# rpi.net
KiCad netlist of a schematic drawn in EAGLE
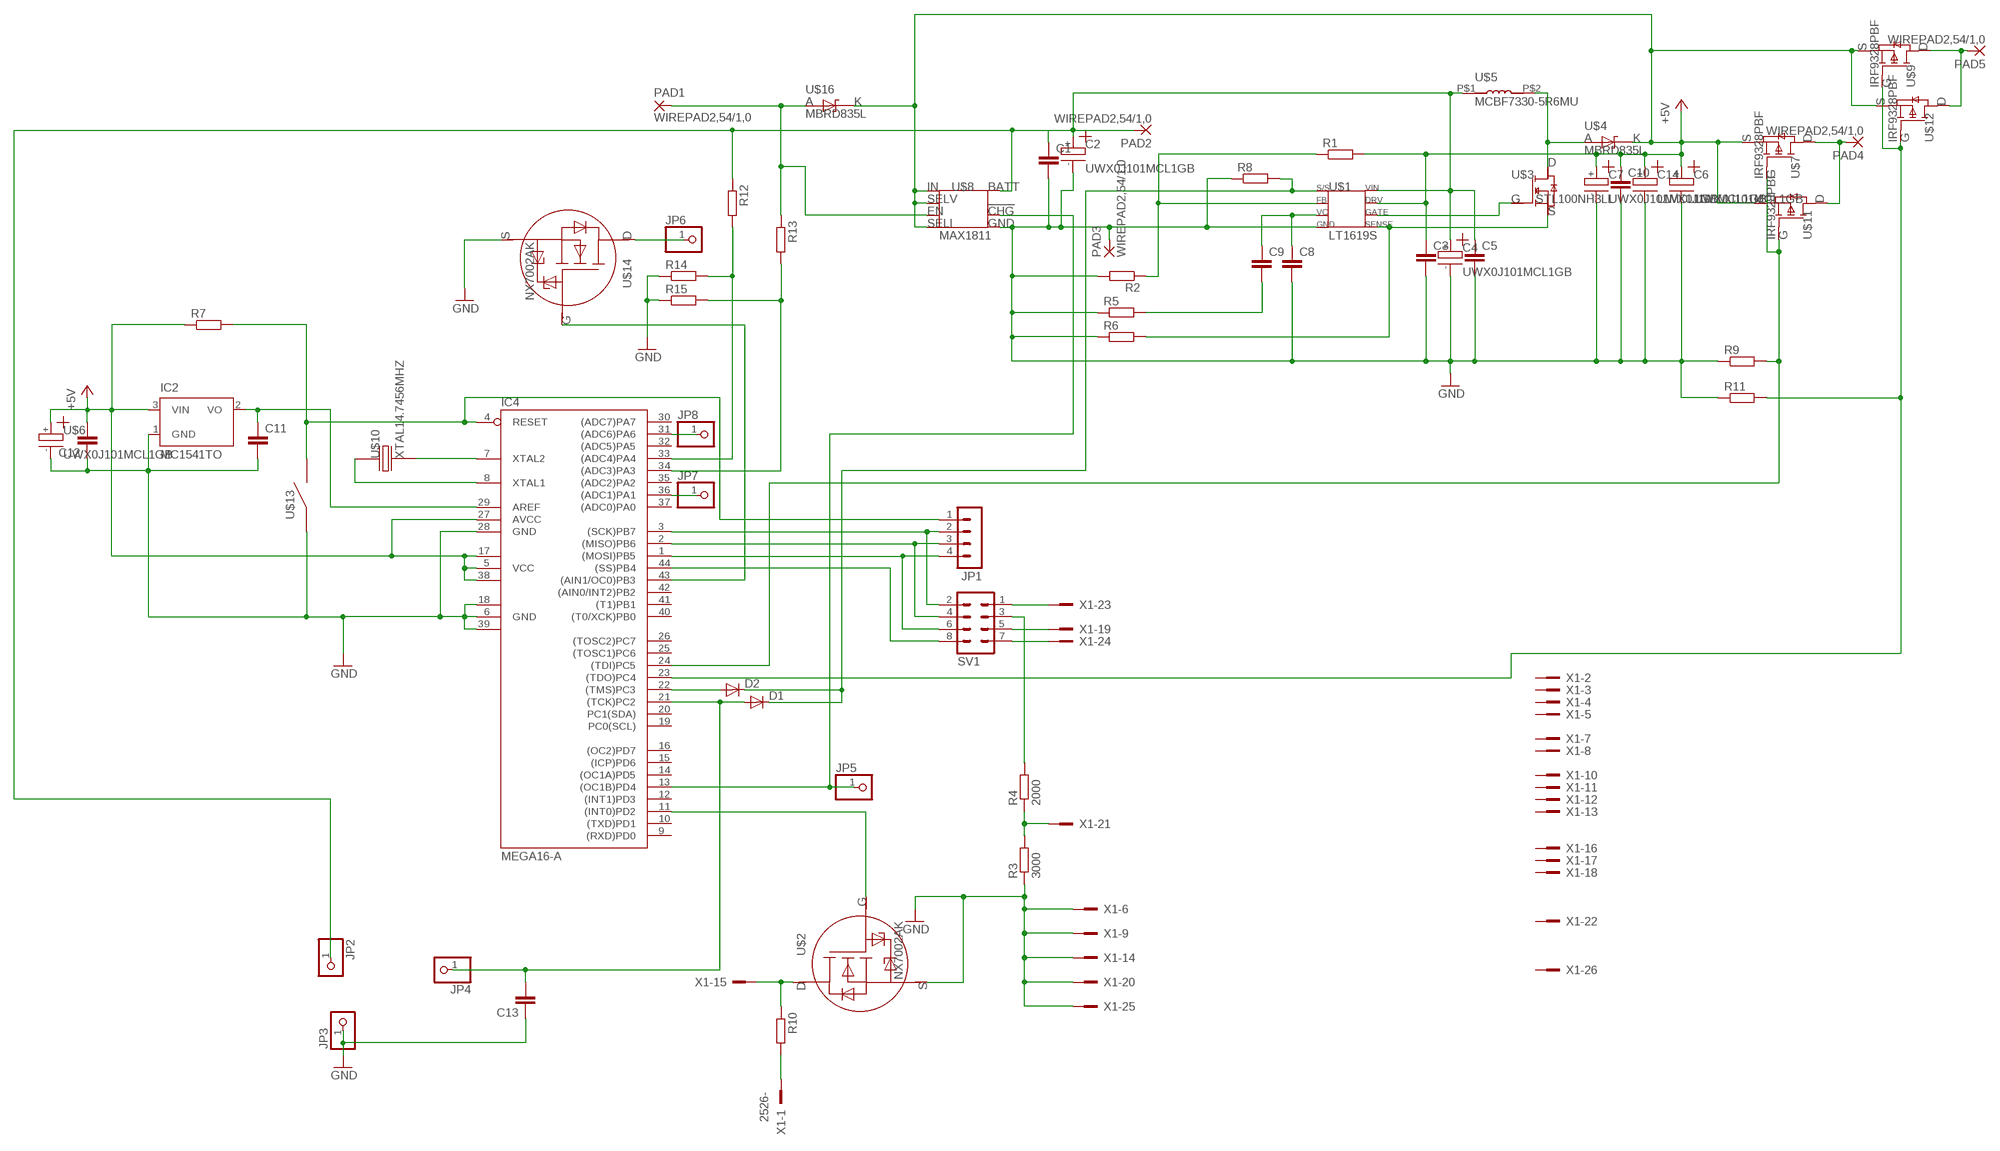
[diagram p0: schematic, sheet 1]

(export (version "E")
  (design (tool "Eeschema 10.0.6"))
  (components
    (comp (ref "C1")
      (value "C-EUC1206")
      (footprint "eagle-import:C1206")
      (libsource (lib "eagle-import") (part "C-EUC1206"))
    )
    (comp (ref "C2")
      (value "UWX0J101MCL1GB")
      (footprint "eagle-import:UWX0J101MCL1GB")
      (libsource (lib "eagle-import") (part "UWX0J101MCL1GB"))
    )
    (comp (ref "C3")
      (value "C-EUC1206")
      (footprint "eagle-import:C1206")
      (libsource (lib "eagle-import") (part "C-EUC1206"))
    )
    (comp (ref "C4")
      (value "UWX0J101MCL1GB")
      (footprint "eagle-import:UWX0J101MCL1GB")
      (libsource (lib "eagle-import") (part "UWX0J101MCL1GB"))
    )
    (comp (ref "C5")
      (value "C-EUC1206")
      (footprint "eagle-import:C1206")
      (libsource (lib "eagle-import") (part "C-EUC1206"))
    )
    (comp (ref "C6")
      (value "UWX0J101MCL1GB")
      (footprint "eagle-import:UWX0J101MCL1GB")
      (libsource (lib "eagle-import") (part "UWX0J101MCL1GB"))
    )
    (comp (ref "C7")
      (value "UWX0J101MCL1GB")
      (footprint "eagle-import:UWX0J101MCL1GB")
      (libsource (lib "eagle-import") (part "UWX0J101MCL1GB"))
    )
    (comp (ref "C8")
      (value "C-EUC1206")
      (footprint "eagle-import:C1206")
      (libsource (lib "eagle-import") (part "C-EUC1206"))
    )
    (comp (ref "C9")
      (value "C-EUC1206")
      (footprint "eagle-import:C1206")
      (libsource (lib "eagle-import") (part "C-EUC1206"))
    )
    (comp (ref "C10")
      (value "C-EUC1206")
      (footprint "eagle-import:C1206")
      (libsource (lib "eagle-import") (part "C-EUC1206"))
    )
    (comp (ref "C11")
      (value "C-EUC1206")
      (footprint "eagle-import:C1206")
      (libsource (lib "eagle-import") (part "C-EUC1206"))
    )
    (comp (ref "C12")
      (value "C-EUC1206")
      (footprint "eagle-import:C1206")
      (libsource (lib "eagle-import") (part "C-EUC1206"))
    )
    (comp (ref "C13")
      (value "C-EUC1206")
      (footprint "eagle-import:C1206")
      (libsource (lib "eagle-import") (part "C-EUC1206"))
    )
    (comp (ref "C14")
      (value "UWX0J101MCL1GB")
      (footprint "eagle-import:UWX0J101MCL1GB")
      (libsource (lib "eagle-import") (part "UWX0J101MCL1GB"))
    )
    (comp (ref "D1")
      (value "DIODE-MINIMELF")
      (footprint "eagle-import:MINIMELF")
      (libsource (lib "eagle-import") (part "DIODE-MINIMELF"))
    )
    (comp (ref "D2")
      (value "DIODE-MINIMELF")
      (footprint "eagle-import:MINIMELF")
      (libsource (lib "eagle-import") (part "DIODE-MINIMELF"))
    )
    (comp (ref "IC2")
      (value "MC1541TO")
      (footprint "eagle-import:TO92")
      (libsource (lib "eagle-import") (part "MC15TO41"))
    )
    (comp (ref "IC4")
      (value "MEGA16-A")
      (footprint "eagle-import:TQFP44")
      (fields (field (name "MPN") "ATMEGA16-16AU"))
      (libsource (lib "eagle-import") (part "MEGA16-A"))
    )
    (comp (ref "JP1")
      (value "MA04-1")
      (footprint "eagle-import:MA04-1")
      (libsource (lib "eagle-import") (part "MA04-1"))
    )
    (comp (ref "JP2")
      (value "PINHD-1X1")
      (footprint "eagle-import:1X01")
      (libsource (lib "eagle-import") (part "PINHD-1X1"))
    )
    (comp (ref "JP3")
      (value "PINHD-1X1")
      (footprint "eagle-import:1X01")
      (libsource (lib "eagle-import") (part "PINHD-1X1"))
    )
    (comp (ref "JP4")
      (value "PINHD-1X1")
      (footprint "eagle-import:1X01")
      (libsource (lib "eagle-import") (part "PINHD-1X1"))
    )
    (comp (ref "JP5")
      (value "PINHD-1X1")
      (footprint "eagle-import:1X01")
      (libsource (lib "eagle-import") (part "PINHD-1X1"))
    )
    (comp (ref "JP6")
      (value "PINHD-1X1")
      (footprint "eagle-import:1X01")
      (libsource (lib "eagle-import") (part "PINHD-1X1"))
    )
    (comp (ref "JP7")
      (value "PINHD-1X1")
      (footprint "eagle-import:1X01")
      (libsource (lib "eagle-import") (part "PINHD-1X1"))
    )
    (comp (ref "JP8")
      (value "PINHD-1X1")
      (footprint "eagle-import:1X01")
      (libsource (lib "eagle-import") (part "PINHD-1X1"))
    )
    (comp (ref "PAD1")
      (value "WIREPAD2,54/1,0")
      (footprint "eagle-import:2,54_1,0")
      (libsource (lib "eagle-import") (part "WIREPAD2,54/1,0"))
    )
    (comp (ref "PAD2")
      (value "WIREPAD2,54/1,0")
      (footprint "eagle-import:2,54_1,0")
      (libsource (lib "eagle-import") (part "WIREPAD2,54/1,0"))
    )
    (comp (ref "PAD3")
      (value "WIREPAD2,54/1,0")
      (footprint "eagle-import:2,54_1,0")
      (libsource (lib "eagle-import") (part "WIREPAD2,54/1,0"))
    )
    (comp (ref "PAD4")
      (value "WIREPAD2,54/1,0")
      (footprint "eagle-import:2,54_1,0")
      (libsource (lib "eagle-import") (part "WIREPAD2,54/1,0"))
    )
    (comp (ref "PAD5")
      (value "WIREPAD2,54/1,0")
      (footprint "eagle-import:2,54_1,0")
      (libsource (lib "eagle-import") (part "WIREPAD2,54/1,0"))
    )
    (comp (ref "R1")
      (value "R-EU_R1206")
      (footprint "eagle-import:R1206")
      (libsource (lib "eagle-import") (part "R-EU_R1206"))
    )
    (comp (ref "R2")
      (value "R-EU_R1206")
      (footprint "eagle-import:R1206")
      (libsource (lib "eagle-import") (part "R-EU_R1206"))
    )
    (comp (ref "R3")
      (value "3000")
      (footprint "eagle-import:R1206")
      (libsource (lib "eagle-import") (part "resistor_R-EU_R1206"))
    )
    (comp (ref "R4")
      (value "2000")
      (footprint "eagle-import:R1206")
      (libsource (lib "eagle-import") (part "resistor_R-EU_R1206"))
    )
    (comp (ref "R5")
      (value "R-EU_R1206")
      (footprint "eagle-import:R1206")
      (libsource (lib "eagle-import") (part "R-EU_R1206"))
    )
    (comp (ref "R6")
      (value "R-EU_R1206")
      (footprint "eagle-import:R1206")
      (libsource (lib "eagle-import") (part "R-EU_R1206"))
    )
    (comp (ref "R7")
      (value "R-EU_R1206")
      (footprint "eagle-import:R1206")
      (libsource (lib "eagle-import") (part "R-EU_R1206"))
    )
    (comp (ref "R8")
      (value "R-EU_R1206")
      (footprint "eagle-import:R1206")
      (libsource (lib "eagle-import") (part "R-EU_R1206"))
    )
    (comp (ref "R9")
      (value "R-EU_R1206")
      (footprint "eagle-import:R1206")
      (libsource (lib "eagle-import") (part "R-EU_R1206"))
    )
    (comp (ref "R10")
      (value "R-EU_R1206")
      (footprint "eagle-import:R1206")
      (libsource (lib "eagle-import") (part "R-EU_R1206"))
    )
    (comp (ref "R11")
      (value "R-EU_R1206")
      (footprint "eagle-import:R1206")
      (libsource (lib "eagle-import") (part "R-EU_R1206"))
    )
    (comp (ref "R12")
      (value "R-EU_R1206")
      (footprint "eagle-import:R1206")
      (libsource (lib "eagle-import") (part "R-EU_R1206"))
    )
    (comp (ref "R13")
      (value "R-EU_R1206")
      (footprint "eagle-import:R1206")
      (libsource (lib "eagle-import") (part "R-EU_R1206"))
    )
    (comp (ref "R14")
      (value "R-EU_R1206")
      (footprint "eagle-import:R1206")
      (libsource (lib "eagle-import") (part "R-EU_R1206"))
    )
    (comp (ref "R15")
      (value "R-EU_R1206")
      (footprint "eagle-import:R1206")
      (libsource (lib "eagle-import") (part "R-EU_R1206"))
    )
    (comp (ref "SV1")
      (value "MA04-2")
      (footprint "eagle-import:MA04-2")
      (libsource (lib "eagle-import") (part "MA04-2"))
    )
    (comp (ref "U$1")
      (value "LT1619S")
      (footprint "eagle-import:SO8")
      (libsource (lib "eagle-import") (part "LT1619S"))
    )
    (comp (ref "U$2")
      (value "NX7002AK")
      (footprint "eagle-import:SOT23")
      (libsource (lib "eagle-import") (part "NX7002AK"))
    )
    (comp (ref "U$3")
      (value "STL100NH3LL")
      (footprint "eagle-import:POWERFLAT6X5")
      (libsource (lib "eagle-import") (part "STL100NH3LL"))
    )
    (comp (ref "U$4")
      (value "MBRD835L")
      (footprint "eagle-import:DPAK")
      (libsource (lib "eagle-import") (part "MBRD835L"))
    )
    (comp (ref "U$5")
      (value "MCBF7330-5R6MU")
      (footprint "eagle-import:MCBF7330-5R6MU")
      (libsource (lib "eagle-import") (part "MCBF7330-5R6MU"))
    )
    (comp (ref "U$6")
      (value "UWX0J101MCL1GB")
      (footprint "eagle-import:UWX0J101MCL1GB")
      (libsource (lib "eagle-import") (part "UWX0J101MCL1GB"))
    )
    (comp (ref "U$7")
      (value "IRF9328PBF")
      (footprint "eagle-import:SO8")
      (libsource (lib "eagle-import") (part "IRF9328PBF"))
    )
    (comp (ref "U$8")
      (value "MAX1811")
      (footprint "eagle-import:SO8")
      (libsource (lib "eagle-import") (part "MAX1811"))
    )
    (comp (ref "U$9")
      (value "IRF9328PBF")
      (footprint "eagle-import:SO8")
      (libsource (lib "eagle-import") (part "IRF9328PBF"))
    )
    (comp (ref "U$10")
      (value "XTAL14.7456MHZ")
      (footprint "eagle-import:HC49-SMD")
      (libsource (lib "eagle-import") (part "XTAL14.7456MHZ"))
    )
    (comp (ref "U$11")
      (value "IRF9328PBF")
      (footprint "eagle-import:SO8")
      (libsource (lib "eagle-import") (part "IRF9328PBF"))
    )
    (comp (ref "U$12")
      (value "IRF9328PBF")
      (footprint "eagle-import:SO8")
      (libsource (lib "eagle-import") (part "IRF9328PBF"))
    )
    (comp (ref "U$13")
      (value "TLACITKO")
      (footprint "eagle-import:TLACITKO")
      (libsource (lib "eagle-import") (part "TLACITKO"))
    )
    (comp (ref "U$14")
      (value "NX7002AK")
      (footprint "eagle-import:SOT23")
      (libsource (lib "eagle-import") (part "NX7002AK"))
    )
    (comp (ref "U$16")
      (value "MBRD835L")
      (footprint "eagle-import:DPAK")
      (libsource (lib "eagle-import") (part "MBRD835L"))
    )
    (comp (ref "X1")
      (value "2526-")
      (footprint "eagle-import:PAK100_2500-26")
      (libsource (lib "eagle-import") (part "2526-"))
    )
  )
  (nets
    (net (code "1") (name "+5V") (class "Default")
      (node (ref "C10") (pin "1") (pinfunction "1_1") (pintype "passive"))
      (node (ref "C12") (pin "2") (pinfunction "2_2") (pintype "passive"))
      (node (ref "C14") (pin "+") (pinfunction "+_+") (pintype "bidirectional"))
      (node (ref "C3") (pin "1") (pinfunction "1_1") (pintype "passive"))
      (node (ref "C6") (pin "+") (pinfunction "+_+") (pintype "bidirectional"))
      (node (ref "C7") (pin "+") (pinfunction "+_+") (pintype "bidirectional"))
      (node (ref "IC2") (pin "3") (pinfunction "VIN_3") (pintype "input"))
      (node (ref "IC4") (pin "17") (pinfunction "VCC1_17") (pintype "power_in"))
      (node (ref "IC4") (pin "27") (pinfunction "AVCC_27") (pintype "power_in"))
      (node (ref "IC4") (pin "38") (pinfunction "VCC2_38") (pintype "power_in"))
      (node (ref "IC4") (pin "5") (pinfunction "VCC_5") (pintype "power_in"))
      (node (ref "R1") (pin "2") (pinfunction "2_2") (pintype "passive"))
      (node (ref "R7") (pin "1") (pinfunction "1_1") (pintype "passive"))
      (node (ref "U$1") (pin "D2") (pinfunction "DRV_D2") (pintype "bidirectional"))
      (node (ref "U$11") (pin "S") (pinfunction "S_S") (pintype "bidirectional"))
      (node (ref "U$11") (pin "S2") (pinfunction "S_S2") (pintype "bidirectional"))
      (node (ref "U$11") (pin "S3") (pinfunction "S_S3") (pintype "bidirectional"))
      (node (ref "U$12") (pin "S") (pinfunction "S_S") (pintype "bidirectional"))
      (node (ref "U$12") (pin "S2") (pinfunction "S_S2") (pintype "bidirectional"))
      (node (ref "U$12") (pin "S3") (pinfunction "S_S3") (pintype "bidirectional"))
      (node (ref "U$16") (pin "4") (pinfunction "K_4") (pintype "bidirectional"))
      (node (ref "U$4") (pin "4") (pinfunction "K_4") (pintype "bidirectional"))
      (node (ref "U$6") (pin "+") (pinfunction "+_+") (pintype "bidirectional"))
      (node (ref "U$7") (pin "S") (pinfunction "S_S") (pintype "bidirectional"))
      (node (ref "U$7") (pin "S2") (pinfunction "S_S2") (pintype "bidirectional"))
      (node (ref "U$7") (pin "S3") (pinfunction "S_S3") (pintype "bidirectional"))
      (node (ref "U$8") (pin "G") (pinfunction "IN_G") (pintype "bidirectional"))
      (node (ref "U$8") (pin "S") (pinfunction "SELV_S") (pintype "bidirectional"))
      (node (ref "U$8") (pin "S2") (pinfunction "SELI_S2") (pintype "bidirectional"))
      (node (ref "U$9") (pin "S") (pinfunction "S_S") (pintype "bidirectional"))
      (node (ref "U$9") (pin "S2") (pinfunction "S_S2") (pintype "bidirectional"))
      (node (ref "U$9") (pin "S3") (pinfunction "S_S3") (pintype "bidirectional"))
    )
    (net (code "2") (name "/XTAL1") (class "Default")
      (node (ref "IC4") (pin "8") (pinfunction "XTAL1_8") (pintype "bidirectional"))
      (node (ref "U$10") (pin "P$1") (pinfunction "P$1_P$1") (pintype "bidirectional"))
    )
    (net (code "3") (name "/XTAL2") (class "Default")
      (node (ref "IC4") (pin "7") (pinfunction "XTAL2_7") (pintype "bidirectional"))
      (node (ref "U$10") (pin "P$2") (pinfunction "P$2_P$2") (pintype "bidirectional"))
    )
    (net (code "4") (name "GND") (class "Default")
      (node (ref "C1") (pin "2") (pinfunction "2_2") (pintype "passive"))
      (node (ref "C10") (pin "2") (pinfunction "2_2") (pintype "passive"))
      (node (ref "C11") (pin "2") (pinfunction "2_2") (pintype "passive"))
      (node (ref "C12") (pin "1") (pinfunction "1_1") (pintype "passive"))
      (node (ref "C13") (pin "1") (pinfunction "1_1") (pintype "passive"))
      (node (ref "C14") (pin "-") (pinfunction "-_-") (pintype "bidirectional"))
      (node (ref "C2") (pin "-") (pinfunction "-_-") (pintype "bidirectional"))
      (node (ref "C3") (pin "2") (pinfunction "2_2") (pintype "passive"))
      (node (ref "C4") (pin "-") (pinfunction "-_-") (pintype "bidirectional"))
      (node (ref "C5") (pin "2") (pinfunction "2_2") (pintype "passive"))
      (node (ref "C6") (pin "-") (pinfunction "-_-") (pintype "bidirectional"))
      (node (ref "C7") (pin "-") (pinfunction "-_-") (pintype "bidirectional"))
      (node (ref "C8") (pin "2") (pinfunction "2_2") (pintype "passive"))
      (node (ref "IC2") (pin "1") (pinfunction "GND_1") (pintype "passive"))
      (node (ref "IC4") (pin "18") (pinfunction "GND1_18") (pintype "power_in"))
      (node (ref "IC4") (pin "28") (pinfunction "GND_28") (pintype "power_in"))
      (node (ref "IC4") (pin "39") (pinfunction "GND2_39") (pintype "power_in"))
      (node (ref "IC4") (pin "6") (pinfunction "GND_6") (pintype "power_in"))
      (node (ref "JP3") (pin "1") (pinfunction "1_1") (pintype "passive"))
      (node (ref "PAD3") (pin "1") (pinfunction "P_1") (pintype "passive"))
      (node (ref "R11") (pin "1") (pinfunction "1_1") (pintype "passive"))
      (node (ref "R14") (pin "1") (pinfunction "1_1") (pintype "passive"))
      (node (ref "R15") (pin "1") (pinfunction "1_1") (pintype "passive"))
      (node (ref "R2") (pin "2") (pinfunction "2_2") (pintype "passive"))
      (node (ref "R3") (pin "1") (pinfunction "1_1") (pintype "passive"))
      (node (ref "R5") (pin "1") (pinfunction "1_1") (pintype "passive"))
      (node (ref "R6") (pin "1") (pinfunction "1_1") (pintype "passive"))
      (node (ref "R8") (pin "1") (pinfunction "1_1") (pintype "passive"))
      (node (ref "R9") (pin "1") (pinfunction "1_1") (pintype "passive"))
      (node (ref "U$1") (pin "G") (pinfunction "GND_G") (pintype "bidirectional"))
      (node (ref "U$13") (pin "P$1") (pinfunction "P$1_P$1") (pintype "bidirectional"))
      (node (ref "U$13") (pin "P$3") (pinfunction "P$1_P$3") (pintype "bidirectional"))
      (node (ref "U$14") (pin "S") (pinfunction "S_S") (pintype "bidirectional"))
      (node (ref "U$2") (pin "S") (pinfunction "S_S") (pintype "bidirectional"))
      (node (ref "U$6") (pin "-") (pinfunction "-_-") (pintype "bidirectional"))
      (node (ref "U$8") (pin "D3") (pinfunction "GND_D3") (pintype "bidirectional"))
      (node (ref "U$8") (pin "S3") (pinfunction "GND_S3") (pintype "bidirectional"))
      (node (ref "X1") (pin "14") (pinfunction "KL_14") (pintype "passive"))
      (node (ref "X1") (pin "20") (pinfunction "KL_20") (pintype "passive"))
      (node (ref "X1") (pin "25") (pinfunction "KL_25") (pintype "passive"))
      (node (ref "X1") (pin "6") (pinfunction "KL_6") (pintype "passive"))
      (node (ref "X1") (pin "9") (pinfunction "KL_9") (pintype "passive"))
    )
    (net (code "5") (name "Net-(C9-Pad2)") (class "Default")
      (node (ref "C9") (pin "2") (pinfunction "2_2") (pintype "passive"))
      (node (ref "R5") (pin "2") (pinfunction "2_2") (pintype "passive"))
    )
    (net (code "6") (name "Net-(IC2-VO)") (class "Default")
      (node (ref "C11") (pin "1") (pinfunction "1_1") (pintype "passive"))
      (node (ref "IC2") (pin "2") (pinfunction "VO_2") (pintype "output"))
      (node (ref "IC4") (pin "29") (pinfunction "AREF_29") (pintype "passive"))
    )
    (net (code "7") (name "Net-(IC4-(ADC1)PA1)") (class "Default")
      (node (ref "IC4") (pin "36") (pinfunction "(ADC1)PA1_36") (pintype "bidirectional"))
      (node (ref "JP7") (pin "1") (pinfunction "1_1") (pintype "passive"))
    )
    (net (code "8") (name "Net-(IC4-(ADC3)PA3)") (class "Default")
      (node (ref "IC4") (pin "34") (pinfunction "(ADC3)PA3_34") (pintype "bidirectional"))
      (node (ref "R13") (pin "2") (pinfunction "2_2") (pintype "passive"))
      (node (ref "R15") (pin "2") (pinfunction "2_2") (pintype "passive"))
    )
    (net (code "9") (name "Net-(IC4-(ADC4)PA4)") (class "Default")
      (node (ref "IC4") (pin "33") (pinfunction "(ADC4)PA4_33") (pintype "bidirectional"))
      (node (ref "R12") (pin "2") (pinfunction "2_2") (pintype "passive"))
      (node (ref "R14") (pin "2") (pinfunction "2_2") (pintype "passive"))
    )
    (net (code "10") (name "Net-(IC4-(ADC6)PA6)") (class "Default")
      (node (ref "IC4") (pin "31") (pinfunction "(ADC6)PA6_31") (pintype "bidirectional"))
      (node (ref "JP8") (pin "1") (pinfunction "1_1") (pintype "passive"))
    )
    (net (code "11") (name "Net-(IC4-(AIN1{slash}OC0)PB3)") (class "Default")
      (node (ref "IC4") (pin "43") (pinfunction "(AIN1/OC0)PB3_43") (pintype "bidirectional"))
      (node (ref "U$14") (pin "G") (pinfunction "G_G") (pintype "bidirectional"))
    )
    (net (code "12") (name "Net-(IC4-(INT0)PD2)") (class "Default")
      (node (ref "IC4") (pin "11") (pinfunction "(INT0)PD2_11") (pintype "bidirectional"))
      (node (ref "U$2") (pin "G") (pinfunction "G_G") (pintype "bidirectional"))
    )
    (net (code "13") (name "Net-(IC4-(MISO)PB6)") (class "Default")
      (node (ref "IC4") (pin "2") (pinfunction "(MISO)PB6_2") (pintype "bidirectional"))
      (node (ref "JP1") (pin "3") (pinfunction "3_3") (pintype "passive"))
      (node (ref "SV1") (pin "4") (pinfunction "4_4") (pintype "passive"))
    )
    (net (code "14") (name "Net-(IC4-(MOSI)PB5)") (class "Default")
      (node (ref "IC4") (pin "1") (pinfunction "(MOSI)PB5_1") (pintype "bidirectional"))
      (node (ref "JP1") (pin "4") (pinfunction "4_4") (pintype "passive"))
      (node (ref "SV1") (pin "6") (pinfunction "6_6") (pintype "passive"))
    )
    (net (code "15") (name "Net-(IC4-(OC1B)PD4)") (class "Default")
      (node (ref "IC4") (pin "13") (pinfunction "(OC1B)PD4_13") (pintype "bidirectional"))
      (node (ref "JP5") (pin "1") (pinfunction "1_1") (pintype "passive"))
      (node (ref "U$8") (pin "D") (pinfunction "~{CHG}_D") (pintype "bidirectional"))
    )
    (net (code "16") (name "Net-(IC4-(SCK)PB7)") (class "Default")
      (node (ref "IC4") (pin "3") (pinfunction "(SCK)PB7_3") (pintype "bidirectional"))
      (node (ref "JP1") (pin "2") (pinfunction "2_2") (pintype "passive"))
      (node (ref "SV1") (pin "2") (pinfunction "2_2") (pintype "passive"))
    )
    (net (code "17") (name "Net-(IC4-(SS)PB4)") (class "Default")
      (node (ref "IC4") (pin "44") (pinfunction "(SS)PB4_44") (pintype "bidirectional"))
      (node (ref "SV1") (pin "8") (pinfunction "8_8") (pintype "passive"))
    )
    (net (code "18") (name "Net-(IC4-(TCK)PC2)") (class "Default")
      (node (ref "C13") (pin "2") (pinfunction "2_2") (pintype "passive"))
      (node (ref "D1") (pin "A") (pinfunction "A_A") (pintype "passive"))
      (node (ref "IC4") (pin "21") (pinfunction "(TCK)PC2_21") (pintype "bidirectional"))
      (node (ref "JP4") (pin "1") (pinfunction "1_1") (pintype "passive"))
    )
    (net (code "19") (name "Net-(IC4-(TDI)PC5)") (class "Default")
      (node (ref "IC4") (pin "24") (pinfunction "(TDI)PC5_24") (pintype "bidirectional"))
      (node (ref "R9") (pin "2") (pinfunction "2_2") (pintype "passive"))
      (node (ref "U$11") (pin "G") (pinfunction "G_G") (pintype "bidirectional"))
      (node (ref "U$7") (pin "G") (pinfunction "G_G") (pintype "bidirectional"))
    )
    (net (code "20") (name "Net-(IC4-(TDO)PC4)") (class "Default")
      (node (ref "IC4") (pin "23") (pinfunction "(TDO)PC4_23") (pintype "bidirectional"))
      (node (ref "R11") (pin "2") (pinfunction "2_2") (pintype "passive"))
      (node (ref "U$12") (pin "G") (pinfunction "G_G") (pintype "bidirectional"))
      (node (ref "U$9") (pin "G") (pinfunction "G_G") (pintype "bidirectional"))
    )
    (net (code "21") (name "Net-(IC4-(TMS)PC3)") (class "Default")
      (node (ref "D2") (pin "A") (pinfunction "A_A") (pintype "passive"))
      (node (ref "IC4") (pin "22") (pinfunction "(TMS)PC3_22") (pintype "bidirectional"))
    )
    (net (code "22") (name "Net-(IC4-RESET)") (class "Default")
      (node (ref "IC4") (pin "4") (pinfunction "RESET_4") (pintype "input"))
      (node (ref "JP1") (pin "1") (pinfunction "1_1") (pintype "passive"))
      (node (ref "R7") (pin "2") (pinfunction "2_2") (pintype "passive"))
      (node (ref "U$13") (pin "P$2") (pinfunction "P$2_P$2") (pintype "bidirectional"))
      (node (ref "U$13") (pin "P$4") (pinfunction "P$2_P$4") (pintype "bidirectional"))
    )
    (net (code "23") (name "Net-(JP6-Pad1)") (class "Default")
      (node (ref "JP6") (pin "1") (pinfunction "1_1") (pintype "passive"))
      (node (ref "U$14") (pin "D") (pinfunction "D_D") (pintype "bidirectional"))
    )
    (net (code "24") (name "Net-(PAD1-P)") (class "Default")
      (node (ref "PAD1") (pin "1") (pinfunction "P_1") (pintype "passive"))
      (node (ref "R13") (pin "1") (pinfunction "1_1") (pintype "passive"))
      (node (ref "U$16") (pin "1") (pinfunction "A_1") (pintype "bidirectional"))
      (node (ref "U$16") (pin "3") (pinfunction "A_3") (pintype "bidirectional"))
      (node (ref "U$8") (pin "D2") (pinfunction "EN_D2") (pintype "bidirectional"))
    )
    (net (code "25") (name "Net-(PAD2-P)") (class "Default")
      (node (ref "C1") (pin "1") (pinfunction "1_1") (pintype "passive"))
      (node (ref "C2") (pin "+") (pinfunction "+_+") (pintype "bidirectional"))
      (node (ref "C4") (pin "+") (pinfunction "+_+") (pintype "bidirectional"))
      (node (ref "C5") (pin "1") (pinfunction "1_1") (pintype "passive"))
      (node (ref "JP2") (pin "1") (pinfunction "1_1") (pintype "passive"))
      (node (ref "PAD2") (pin "1") (pinfunction "P_1") (pintype "passive"))
      (node (ref "R12") (pin "1") (pinfunction "1_1") (pintype "passive"))
      (node (ref "U$1") (pin "D") (pinfunction "VIN_D") (pintype "bidirectional"))
      (node (ref "U$5") (pin "P$1") (pinfunction "P$1_P$1") (pintype "bidirectional"))
      (node (ref "U$8") (pin "D4") (pinfunction "BATT_D4") (pintype "bidirectional"))
    )
    (net (code "26") (name "Net-(PAD4-P)") (class "Default")
      (node (ref "PAD4") (pin "1") (pinfunction "P_1") (pintype "passive"))
      (node (ref "U$11") (pin "D") (pinfunction "D_D") (pintype "bidirectional"))
      (node (ref "U$11") (pin "D2") (pinfunction "D_D2") (pintype "bidirectional"))
      (node (ref "U$11") (pin "D3") (pinfunction "D_D3") (pintype "bidirectional"))
      (node (ref "U$11") (pin "D4") (pinfunction "D_D4") (pintype "bidirectional"))
      (node (ref "U$7") (pin "D") (pinfunction "D_D") (pintype "bidirectional"))
      (node (ref "U$7") (pin "D2") (pinfunction "D_D2") (pintype "bidirectional"))
      (node (ref "U$7") (pin "D3") (pinfunction "D_D3") (pintype "bidirectional"))
      (node (ref "U$7") (pin "D4") (pinfunction "D_D4") (pintype "bidirectional"))
    )
    (net (code "27") (name "Net-(PAD5-P)") (class "Default")
      (node (ref "PAD5") (pin "1") (pinfunction "P_1") (pintype "passive"))
      (node (ref "U$12") (pin "D") (pinfunction "D_D") (pintype "bidirectional"))
      (node (ref "U$12") (pin "D2") (pinfunction "D_D2") (pintype "bidirectional"))
      (node (ref "U$12") (pin "D3") (pinfunction "D_D3") (pintype "bidirectional"))
      (node (ref "U$12") (pin "D4") (pinfunction "D_D4") (pintype "bidirectional"))
      (node (ref "U$9") (pin "D") (pinfunction "D_D") (pintype "bidirectional"))
      (node (ref "U$9") (pin "D2") (pinfunction "D_D2") (pintype "bidirectional"))
      (node (ref "U$9") (pin "D3") (pinfunction "D_D3") (pintype "bidirectional"))
      (node (ref "U$9") (pin "D4") (pinfunction "D_D4") (pintype "bidirectional"))
    )
    (net (code "28") (name "Net-(R4-Pad2)") (class "Default")
      (node (ref "R4") (pin "2") (pinfunction "2_2") (pintype "passive"))
      (node (ref "SV1") (pin "3") (pinfunction "3_3") (pintype "passive"))
    )
    (net (code "29") (name "Net-(U$1-FB)") (class "Default")
      (node (ref "R1") (pin "1") (pinfunction "1_1") (pintype "passive"))
      (node (ref "R2") (pin "1") (pinfunction "1_1") (pintype "passive"))
      (node (ref "U$1") (pin "S2") (pinfunction "FB_S2") (pintype "bidirectional"))
    )
    (net (code "30") (name "Net-(U$1-GATE)") (class "Default")
      (node (ref "U$1") (pin "D3") (pinfunction "GATE_D3") (pintype "bidirectional"))
      (node (ref "U$3") (pin "4") (pinfunction "G_4") (pintype "bidirectional"))
    )
    (net (code "31") (name "Net-(U$1-SENSE)") (class "Default")
      (node (ref "R6") (pin "2") (pinfunction "2_2") (pintype "passive"))
      (node (ref "U$1") (pin "D4") (pinfunction "SENSE_D4") (pintype "bidirectional"))
      (node (ref "U$3") (pin "1") (pinfunction "S_1") (pintype "bidirectional"))
      (node (ref "U$3") (pin "2") (pinfunction "S_2") (pintype "bidirectional"))
      (node (ref "U$3") (pin "3") (pinfunction "S_3") (pintype "bidirectional"))
    )
    (net (code "32") (name "Net-(U$1-S{slash}S)") (class "Default")
      (node (ref "D1") (pin "C") (pinfunction "C_C") (pintype "passive"))
      (node (ref "D2") (pin "C") (pinfunction "C_C") (pintype "passive"))
      (node (ref "R8") (pin "2") (pinfunction "2_2") (pintype "passive"))
      (node (ref "U$1") (pin "S") (pinfunction "S/S_S") (pintype "bidirectional"))
    )
    (net (code "33") (name "Net-(U$1-VC)") (class "Default")
      (node (ref "C8") (pin "1") (pinfunction "1_1") (pintype "passive"))
      (node (ref "C9") (pin "1") (pinfunction "1_1") (pintype "passive"))
      (node (ref "U$1") (pin "S3") (pinfunction "VC_S3") (pintype "bidirectional"))
    )
    (net (code "34") (name "Net-(U$3-D)") (class "Default")
      (node (ref "U$3") (pin "5") (pinfunction "D_5") (pintype "bidirectional"))
      (node (ref "U$4") (pin "1") (pinfunction "A_1") (pintype "bidirectional"))
      (node (ref "U$4") (pin "3") (pinfunction "A_3") (pintype "bidirectional"))
      (node (ref "U$5") (pin "P$2") (pinfunction "P$2_P$2") (pintype "bidirectional"))
    )
    (net (code "35") (name "Net-(X1A-KL)") (class "Default")
      (node (ref "R10") (pin "2") (pinfunction "2_2") (pintype "passive"))
      (node (ref "X1") (pin "1") (pinfunction "KL_1") (pintype "passive"))
    )
    (net (code "36") (name "Net-(X1G-KL)") (class "Default")
      (node (ref "R10") (pin "1") (pinfunction "1_1") (pintype "passive"))
      (node (ref "U$2") (pin "D") (pinfunction "D_D") (pintype "bidirectional"))
      (node (ref "X1") (pin "15") (pinfunction "KL_15") (pintype "passive"))
    )
    (net (code "37") (name "Net-(X1K-KL)") (class "Default")
      (node (ref "SV1") (pin "5") (pinfunction "5_5") (pintype "passive"))
      (node (ref "X1") (pin "19") (pinfunction "KL_19") (pintype "passive"))
    )
    (net (code "38") (name "Net-(X1N-KL)") (class "Default")
      (node (ref "R3") (pin "2") (pinfunction "2_2") (pintype "passive"))
      (node (ref "R4") (pin "1") (pinfunction "1_1") (pintype "passive"))
      (node (ref "X1") (pin "21") (pinfunction "KL_21") (pintype "passive"))
    )
    (net (code "39") (name "Net-(X1P-KL)") (class "Default")
      (node (ref "SV1") (pin "1") (pinfunction "1_1") (pintype "passive"))
      (node (ref "X1") (pin "23") (pinfunction "KL_23") (pintype "passive"))
    )
    (net (code "40") (name "Net-(X1Q-KL)") (class "Default")
      (node (ref "SV1") (pin "7") (pinfunction "7_7") (pintype "passive"))
      (node (ref "X1") (pin "24") (pinfunction "KL_24") (pintype "passive"))
    )
    (net (code "41") (name "unconnected-(IC4-(ADC0)PA0-Pad37)") (class "Default")
      (node (ref "IC4") (pin "37") (pinfunction "(ADC0)PA0_37") (pintype "bidirectional"))
    )
    (net (code "42") (name "unconnected-(IC4-(ADC2)PA2-Pad35)") (class "Default")
      (node (ref "IC4") (pin "35") (pinfunction "(ADC2)PA2_35") (pintype "bidirectional"))
    )
    (net (code "43") (name "unconnected-(IC4-(ADC5)PA5-Pad32)") (class "Default")
      (node (ref "IC4") (pin "32") (pinfunction "(ADC5)PA5_32") (pintype "bidirectional"))
    )
    (net (code "44") (name "unconnected-(IC4-(ADC7)PA7-Pad30)") (class "Default")
      (node (ref "IC4") (pin "30") (pinfunction "(ADC7)PA7_30") (pintype "bidirectional"))
    )
    (net (code "45") (name "unconnected-(IC4-(AIN0{slash}INT2)PB2-Pad42)") (class "Default")
      (node (ref "IC4") (pin "42") (pinfunction "(AIN0/INT2)PB2_42") (pintype "bidirectional"))
    )
    (net (code "46") (name "unconnected-(IC4-(ICP)PD6-Pad15)") (class "Default")
      (node (ref "IC4") (pin "15") (pinfunction "(ICP)PD6_15") (pintype "bidirectional"))
    )
    (net (code "47") (name "unconnected-(IC4-(INT1)PD3-Pad12)") (class "Default")
      (node (ref "IC4") (pin "12") (pinfunction "(INT1)PD3_12") (pintype "bidirectional"))
    )
    (net (code "48") (name "unconnected-(IC4-(OC1A)PD5-Pad14)") (class "Default")
      (node (ref "IC4") (pin "14") (pinfunction "(OC1A)PD5_14") (pintype "bidirectional"))
    )
    (net (code "49") (name "unconnected-(IC4-(OC2)PD7-Pad16)") (class "Default")
      (node (ref "IC4") (pin "16") (pinfunction "(OC2)PD7_16") (pintype "bidirectional"))
    )
    (net (code "50") (name "unconnected-(IC4-(RXD)PD0-Pad9)") (class "Default")
      (node (ref "IC4") (pin "9") (pinfunction "(RXD)PD0_9") (pintype "bidirectional"))
    )
    (net (code "51") (name "unconnected-(IC4-(T0{slash}XCK)PB0-Pad40)") (class "Default")
      (node (ref "IC4") (pin "40") (pinfunction "(T0/XCK)PB0_40") (pintype "bidirectional"))
    )
    (net (code "52") (name "unconnected-(IC4-(T1)PB1-Pad41)") (class "Default")
      (node (ref "IC4") (pin "41") (pinfunction "(T1)PB1_41") (pintype "bidirectional"))
    )
    (net (code "53") (name "unconnected-(IC4-(TOSC1)PC6-Pad25)") (class "Default")
      (node (ref "IC4") (pin "25") (pinfunction "(TOSC1)PC6_25") (pintype "bidirectional"))
    )
    (net (code "54") (name "unconnected-(IC4-(TOSC2)PC7-Pad26)") (class "Default")
      (node (ref "IC4") (pin "26") (pinfunction "(TOSC2)PC7_26") (pintype "bidirectional"))
    )
    (net (code "55") (name "unconnected-(IC4-(TXD)PD1-Pad10)") (class "Default")
      (node (ref "IC4") (pin "10") (pinfunction "(TXD)PD1_10") (pintype "bidirectional"))
    )
    (net (code "56") (name "unconnected-(IC4-PC0(SCL)-Pad19)") (class "Default")
      (node (ref "IC4") (pin "19") (pinfunction "PC0(SCL)_19") (pintype "bidirectional"))
    )
    (net (code "57") (name "unconnected-(IC4-PC1(SDA)-Pad20)") (class "Default")
      (node (ref "IC4") (pin "20") (pinfunction "PC1(SDA)_20") (pintype "bidirectional"))
    )
    (net (code "58") (name "unconnected-(X1B-KL-Pad10)") (class "Default")
      (node (ref "X1") (pin "10") (pinfunction "KL_10") (pintype "passive"))
    )
    (net (code "59") (name "unconnected-(X1C-KL-Pad11)") (class "Default")
      (node (ref "X1") (pin "11") (pinfunction "KL_11") (pintype "passive"))
    )
    (net (code "60") (name "unconnected-(X1D-KL-Pad12)") (class "Default")
      (node (ref "X1") (pin "12") (pinfunction "KL_12") (pintype "passive"))
    )
    (net (code "61") (name "unconnected-(X1E-KL-Pad13)") (class "Default")
      (node (ref "X1") (pin "13") (pinfunction "KL_13") (pintype "passive"))
    )
    (net (code "62") (name "unconnected-(X1H-KL-Pad16)") (class "Default")
      (node (ref "X1") (pin "16") (pinfunction "KL_16") (pintype "passive"))
    )
    (net (code "63") (name "unconnected-(X1I-KL-Pad17)") (class "Default")
      (node (ref "X1") (pin "17") (pinfunction "KL_17") (pintype "passive"))
    )
    (net (code "64") (name "unconnected-(X1J-KL-Pad18)") (class "Default")
      (node (ref "X1") (pin "18") (pinfunction "KL_18") (pintype "passive"))
    )
    (net (code "65") (name "unconnected-(X1L-KL-Pad2)") (class "Default")
      (node (ref "X1") (pin "2") (pinfunction "KL_2") (pintype "passive"))
    )
    (net (code "66") (name "unconnected-(X1O-KL-Pad22)") (class "Default")
      (node (ref "X1") (pin "22") (pinfunction "KL_22") (pintype "passive"))
    )
    (net (code "67") (name "unconnected-(X1S-KL-Pad26)") (class "Default")
      (node (ref "X1") (pin "26") (pinfunction "KL_26") (pintype "passive"))
    )
    (net (code "68") (name "unconnected-(X1T-KL-Pad3)") (class "Default")
      (node (ref "X1") (pin "3") (pinfunction "KL_3") (pintype "passive"))
    )
    (net (code "69") (name "unconnected-(X1U-KL-Pad4)") (class "Default")
      (node (ref "X1") (pin "4") (pinfunction "KL_4") (pintype "passive"))
    )
    (net (code "70") (name "unconnected-(X1V-KL-Pad5)") (class "Default")
      (node (ref "X1") (pin "5") (pinfunction "KL_5") (pintype "passive"))
    )
    (net (code "71") (name "unconnected-(X1X-KL-Pad7)") (class "Default")
      (node (ref "X1") (pin "7") (pinfunction "KL_7") (pintype "passive"))
    )
    (net (code "72") (name "unconnected-(X1Y-KL-Pad8)") (class "Default")
      (node (ref "X1") (pin "8") (pinfunction "KL_8") (pintype "passive"))
    )
  )
)
